# low-voltage-shutoff.net
KiCad netlist of a schematic drawn in EAGLE
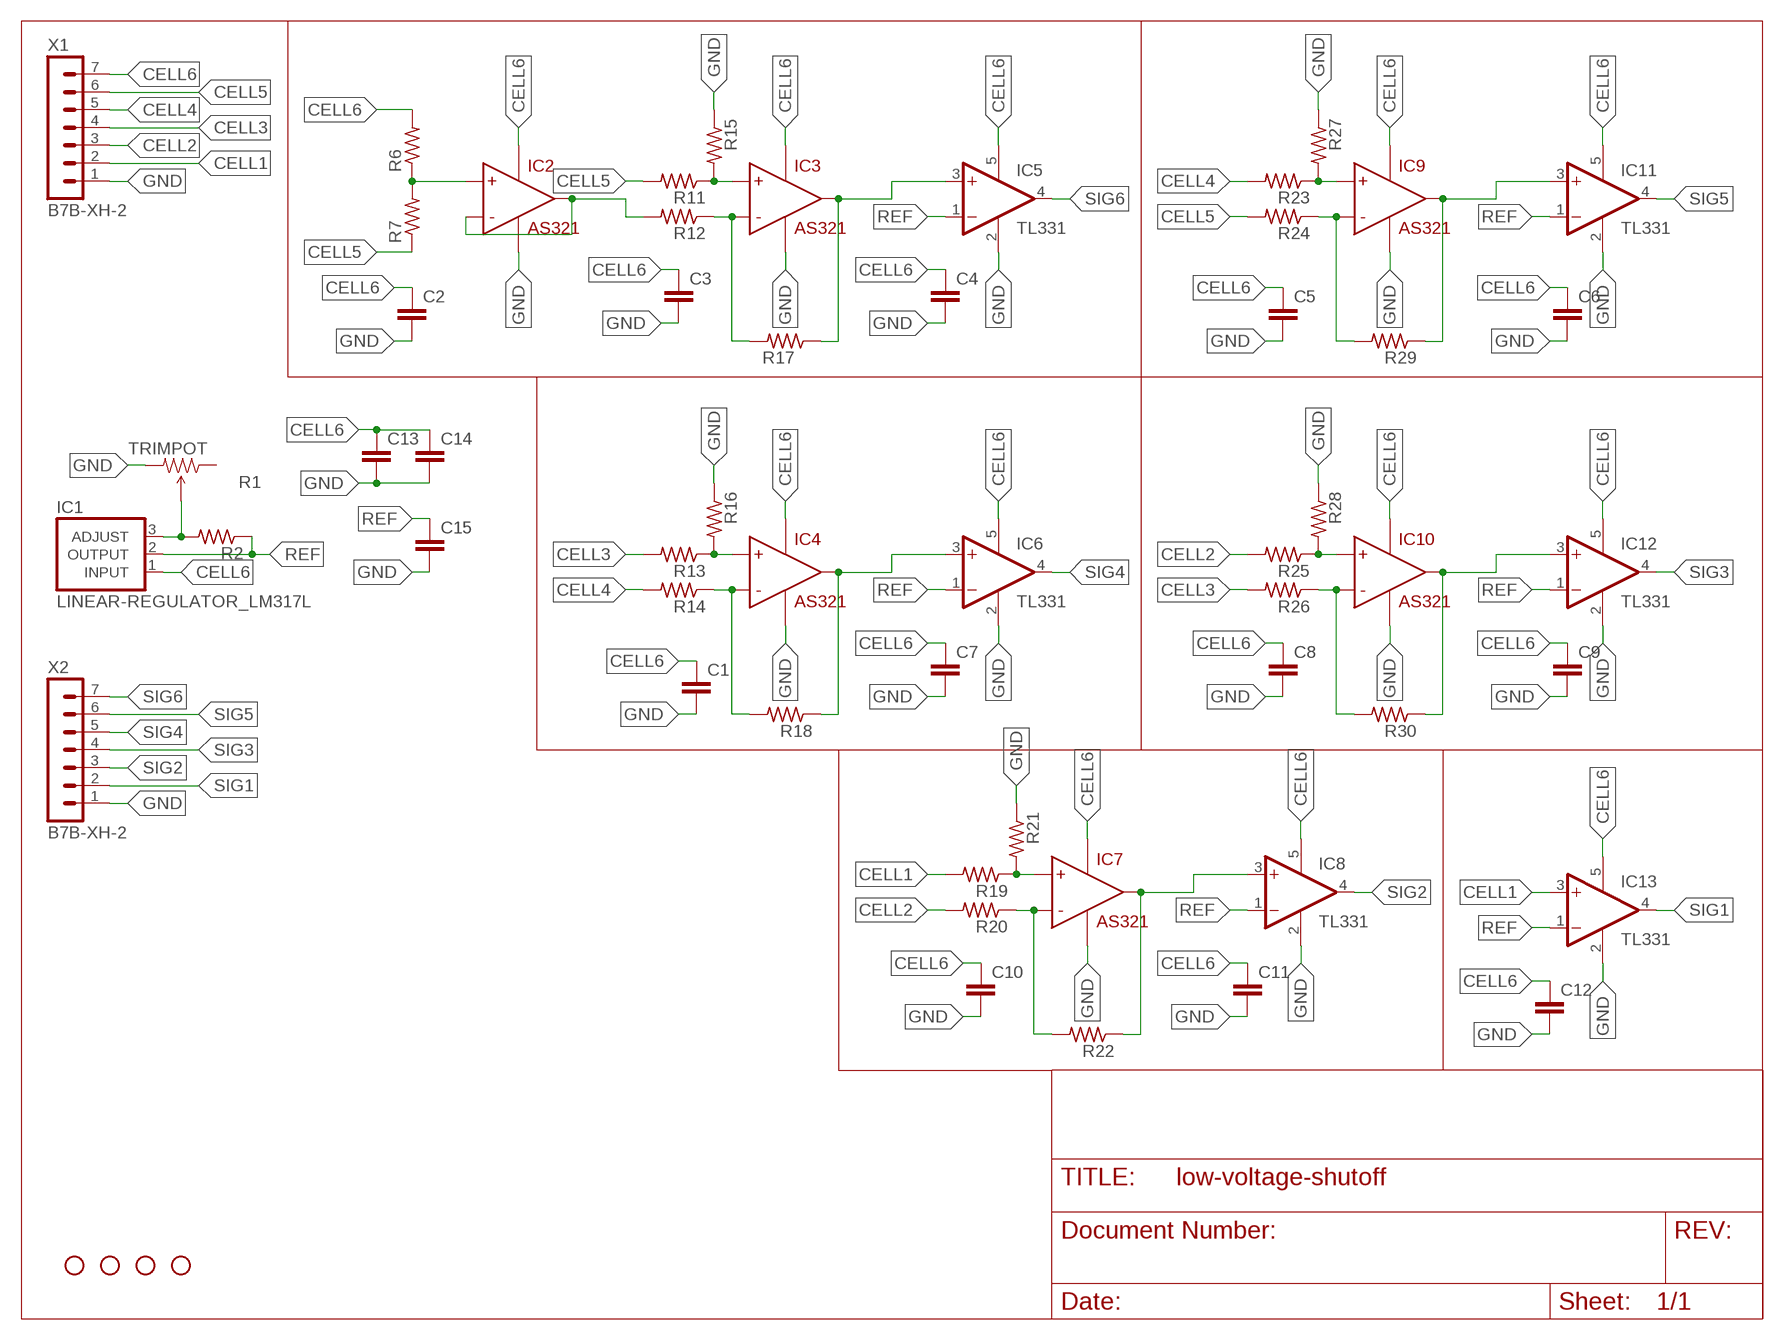
[diagram p0: schematic, sheet 1]

(export (version "E")
  (design (tool "Eeschema 10.0.6"))
  (components
    (comp (ref "C1")
      (value "CAPACITOR_0805")
      (footprint "eagle-import:0805")
      (libsource (lib "eagle-import") (part "CAPACITOR_0805"))
    )
    (comp (ref "C2")
      (value "CAPACITOR_0805")
      (footprint "eagle-import:0805")
      (libsource (lib "eagle-import") (part "CAPACITOR_0805"))
    )
    (comp (ref "C3")
      (value "CAPACITOR_0805")
      (footprint "eagle-import:0805")
      (libsource (lib "eagle-import") (part "CAPACITOR_0805"))
    )
    (comp (ref "C4")
      (value "CAPACITOR_0805")
      (footprint "eagle-import:0805")
      (libsource (lib "eagle-import") (part "CAPACITOR_0805"))
    )
    (comp (ref "C5")
      (value "CAPACITOR_0805")
      (footprint "eagle-import:0805")
      (libsource (lib "eagle-import") (part "CAPACITOR_0805"))
    )
    (comp (ref "C6")
      (value "CAPACITOR_0805")
      (footprint "eagle-import:0805")
      (libsource (lib "eagle-import") (part "CAPACITOR_0805"))
    )
    (comp (ref "C7")
      (value "CAPACITOR_0805")
      (footprint "eagle-import:0805")
      (libsource (lib "eagle-import") (part "CAPACITOR_0805"))
    )
    (comp (ref "C8")
      (value "CAPACITOR_0805")
      (footprint "eagle-import:0805")
      (libsource (lib "eagle-import") (part "CAPACITOR_0805"))
    )
    (comp (ref "C9")
      (value "CAPACITOR_0805")
      (footprint "eagle-import:0805")
      (libsource (lib "eagle-import") (part "CAPACITOR_0805"))
    )
    (comp (ref "C10")
      (value "CAPACITOR_0805")
      (footprint "eagle-import:0805")
      (libsource (lib "eagle-import") (part "CAPACITOR_0805"))
    )
    (comp (ref "C11")
      (value "CAPACITOR_0805")
      (footprint "eagle-import:0805")
      (libsource (lib "eagle-import") (part "CAPACITOR_0805"))
    )
    (comp (ref "C12")
      (value "CAPACITOR_0805")
      (footprint "eagle-import:0805")
      (libsource (lib "eagle-import") (part "CAPACITOR_0805"))
    )
    (comp (ref "C13")
      (value "CAPACITOR_0805")
      (footprint "eagle-import:0805")
      (libsource (lib "eagle-import") (part "CAPACITOR_0805"))
    )
    (comp (ref "C14")
      (value "CAPACITOR_0805")
      (footprint "eagle-import:0805")
      (libsource (lib "eagle-import") (part "CAPACITOR_0805"))
    )
    (comp (ref "C15")
      (value "CAPACITOR_0805")
      (footprint "eagle-import:0805")
      (libsource (lib "eagle-import") (part "CAPACITOR_0805"))
    )
    (comp (ref "H1")
      (value "STAND-OFF")
      (footprint "eagle-import:STAND-OFF")
      (libsource (lib "eagle-import") (part "STAND-OFF"))
    )
    (comp (ref "H2")
      (value "STAND-OFF")
      (footprint "eagle-import:STAND-OFF")
      (libsource (lib "eagle-import") (part "STAND-OFF"))
    )
    (comp (ref "H3")
      (value "STAND-OFF")
      (footprint "eagle-import:STAND-OFF")
      (libsource (lib "eagle-import") (part "STAND-OFF"))
    )
    (comp (ref "H4")
      (value "STAND-OFF")
      (footprint "eagle-import:STAND-OFF")
      (libsource (lib "eagle-import") (part "STAND-OFF"))
    )
    (comp (ref "IC1")
      (value "LINEAR-REGULATOR_LM317L")
      (footprint "eagle-import:TO92")
      (libsource (lib "eagle-import") (part "LINEAR-REGULATOR_LM317L"))
    )
    (comp (ref "IC2")
      (value "AS321")
      (footprint "eagle-import:AS321")
      (libsource (lib "eagle-import") (part "AS321"))
    )
    (comp (ref "IC3")
      (value "AS321")
      (footprint "eagle-import:AS321")
      (libsource (lib "eagle-import") (part "AS321"))
    )
    (comp (ref "IC4")
      (value "AS321")
      (footprint "eagle-import:AS321")
      (libsource (lib "eagle-import") (part "AS321"))
    )
    (comp (ref "IC5")
      (value "TL331")
      (footprint "eagle-import:DBV-R-PDSO-G5")
      (libsource (lib "eagle-import") (part "TL331"))
    )
    (comp (ref "IC6")
      (value "TL331")
      (footprint "eagle-import:DBV-R-PDSO-G5")
      (libsource (lib "eagle-import") (part "TL331"))
    )
    (comp (ref "IC7")
      (value "AS321")
      (footprint "eagle-import:AS321")
      (libsource (lib "eagle-import") (part "AS321"))
    )
    (comp (ref "IC8")
      (value "TL331")
      (footprint "eagle-import:DBV-R-PDSO-G5")
      (libsource (lib "eagle-import") (part "TL331"))
    )
    (comp (ref "IC9")
      (value "AS321")
      (footprint "eagle-import:AS321")
      (libsource (lib "eagle-import") (part "AS321"))
    )
    (comp (ref "IC10")
      (value "AS321")
      (footprint "eagle-import:AS321")
      (libsource (lib "eagle-import") (part "AS321"))
    )
    (comp (ref "IC11")
      (value "TL331")
      (footprint "eagle-import:DBV-R-PDSO-G5")
      (libsource (lib "eagle-import") (part "TL331"))
    )
    (comp (ref "IC12")
      (value "TL331")
      (footprint "eagle-import:DBV-R-PDSO-G5")
      (libsource (lib "eagle-import") (part "TL331"))
    )
    (comp (ref "IC13")
      (value "TL331")
      (footprint "eagle-import:DBV-R-PDSO-G5")
      (libsource (lib "eagle-import") (part "TL331"))
    )
    (comp (ref "R1")
      (value "TRIMPOT")
      (footprint "eagle-import:490-2877-ND")
      (libsource (lib "eagle-import") (part "TRIMPOT"))
    )
    (comp (ref "R2")
      (value "R-US_R0805")
      (footprint "eagle-import:R0805")
      (libsource (lib "eagle-import") (part "R-US_R0805"))
    )
    (comp (ref "R6")
      (value "R-US_R0805")
      (footprint "eagle-import:R0805")
      (libsource (lib "eagle-import") (part "R-US_R0805"))
    )
    (comp (ref "R7")
      (value "R-US_R0805")
      (footprint "eagle-import:R0805")
      (libsource (lib "eagle-import") (part "R-US_R0805"))
    )
    (comp (ref "R11")
      (value "R-US_R0805")
      (footprint "eagle-import:R0805")
      (libsource (lib "eagle-import") (part "R-US_R0805"))
    )
    (comp (ref "R12")
      (value "R-US_R0805")
      (footprint "eagle-import:R0805")
      (libsource (lib "eagle-import") (part "R-US_R0805"))
    )
    (comp (ref "R13")
      (value "R-US_R0805")
      (footprint "eagle-import:R0805")
      (libsource (lib "eagle-import") (part "R-US_R0805"))
    )
    (comp (ref "R14")
      (value "R-US_R0805")
      (footprint "eagle-import:R0805")
      (libsource (lib "eagle-import") (part "R-US_R0805"))
    )
    (comp (ref "R15")
      (value "R-US_R0805")
      (footprint "eagle-import:R0805")
      (libsource (lib "eagle-import") (part "R-US_R0805"))
    )
    (comp (ref "R16")
      (value "R-US_R0805")
      (footprint "eagle-import:R0805")
      (libsource (lib "eagle-import") (part "R-US_R0805"))
    )
    (comp (ref "R17")
      (value "R-US_R0805")
      (footprint "eagle-import:R0805")
      (libsource (lib "eagle-import") (part "R-US_R0805"))
    )
    (comp (ref "R18")
      (value "R-US_R0805")
      (footprint "eagle-import:R0805")
      (libsource (lib "eagle-import") (part "R-US_R0805"))
    )
    (comp (ref "R19")
      (value "R-US_R0805")
      (footprint "eagle-import:R0805")
      (libsource (lib "eagle-import") (part "R-US_R0805"))
    )
    (comp (ref "R20")
      (value "R-US_R0805")
      (footprint "eagle-import:R0805")
      (libsource (lib "eagle-import") (part "R-US_R0805"))
    )
    (comp (ref "R21")
      (value "R-US_R0805")
      (footprint "eagle-import:R0805")
      (libsource (lib "eagle-import") (part "R-US_R0805"))
    )
    (comp (ref "R22")
      (value "R-US_R0805")
      (footprint "eagle-import:R0805")
      (libsource (lib "eagle-import") (part "R-US_R0805"))
    )
    (comp (ref "R23")
      (value "R-US_R0805")
      (footprint "eagle-import:R0805")
      (libsource (lib "eagle-import") (part "R-US_R0805"))
    )
    (comp (ref "R24")
      (value "R-US_R0805")
      (footprint "eagle-import:R0805")
      (libsource (lib "eagle-import") (part "R-US_R0805"))
    )
    (comp (ref "R25")
      (value "R-US_R0805")
      (footprint "eagle-import:R0805")
      (libsource (lib "eagle-import") (part "R-US_R0805"))
    )
    (comp (ref "R26")
      (value "R-US_R0805")
      (footprint "eagle-import:R0805")
      (libsource (lib "eagle-import") (part "R-US_R0805"))
    )
    (comp (ref "R27")
      (value "R-US_R0805")
      (footprint "eagle-import:R0805")
      (libsource (lib "eagle-import") (part "R-US_R0805"))
    )
    (comp (ref "R28")
      (value "R-US_R0805")
      (footprint "eagle-import:R0805")
      (libsource (lib "eagle-import") (part "R-US_R0805"))
    )
    (comp (ref "R29")
      (value "R-US_R0805")
      (footprint "eagle-import:R0805")
      (libsource (lib "eagle-import") (part "R-US_R0805"))
    )
    (comp (ref "R30")
      (value "R-US_R0805")
      (footprint "eagle-import:R0805")
      (libsource (lib "eagle-import") (part "R-US_R0805"))
    )
    (comp (ref "X1")
      (value "B7B-XH-2")
      (footprint "eagle-import:B7B-XH-A")
      (libsource (lib "eagle-import") (part "B7B-XH-2"))
    )
    (comp (ref "X2")
      (value "B7B-XH-2")
      (footprint "eagle-import:B7B-XH-A")
      (libsource (lib "eagle-import") (part "B7B-XH-2"))
    )
  )
  (nets
    (net (code "1") (name "CELL1") (class "Default")
      (node (ref "IC13") (pin "3") (pinfunction "+IN_3") (pintype "input"))
      (node (ref "R19") (pin "2") (pinfunction "2_2") (pintype "passive"))
      (node (ref "X1") (pin "2") (pinfunction "2_2") (pintype "passive"))
    )
    (net (code "2") (name "CELL2") (class "Default")
      (node (ref "R20") (pin "2") (pinfunction "2_2") (pintype "passive"))
      (node (ref "R25") (pin "2") (pinfunction "2_2") (pintype "passive"))
      (node (ref "X1") (pin "3") (pinfunction "3_3") (pintype "passive"))
    )
    (net (code "3") (name "CELL3") (class "Default")
      (node (ref "R13") (pin "2") (pinfunction "2_2") (pintype "passive"))
      (node (ref "R26") (pin "2") (pinfunction "2_2") (pintype "passive"))
      (node (ref "X1") (pin "4") (pinfunction "4_4") (pintype "passive"))
    )
    (net (code "4") (name "CELL4") (class "Default")
      (node (ref "R14") (pin "2") (pinfunction "2_2") (pintype "passive"))
      (node (ref "R23") (pin "2") (pinfunction "2_2") (pintype "passive"))
      (node (ref "X1") (pin "5") (pinfunction "5_5") (pintype "passive"))
    )
    (net (code "5") (name "CELL5") (class "Default")
      (node (ref "R11") (pin "2") (pinfunction "2_2") (pintype "passive"))
      (node (ref "R24") (pin "2") (pinfunction "2_2") (pintype "passive"))
      (node (ref "R7") (pin "1") (pinfunction "1_1") (pintype "passive"))
      (node (ref "X1") (pin "6") (pinfunction "6_6") (pintype "passive"))
    )
    (net (code "6") (name "CELL6") (class "Default")
      (node (ref "C1") (pin "1") (pinfunction "1_1") (pintype "passive"))
      (node (ref "C10") (pin "1") (pinfunction "1_1") (pintype "passive"))
      (node (ref "C11") (pin "1") (pinfunction "1_1") (pintype "passive"))
      (node (ref "C12") (pin "1") (pinfunction "1_1") (pintype "passive"))
      (node (ref "C13") (pin "1") (pinfunction "1_1") (pintype "passive"))
      (node (ref "C14") (pin "1") (pinfunction "1_1") (pintype "passive"))
      (node (ref "C2") (pin "1") (pinfunction "1_1") (pintype "passive"))
      (node (ref "C3") (pin "1") (pinfunction "1_1") (pintype "passive"))
      (node (ref "C4") (pin "1") (pinfunction "1_1") (pintype "passive"))
      (node (ref "C5") (pin "1") (pinfunction "1_1") (pintype "passive"))
      (node (ref "C6") (pin "1") (pinfunction "1_1") (pintype "passive"))
      (node (ref "C7") (pin "1") (pinfunction "1_1") (pintype "passive"))
      (node (ref "C8") (pin "1") (pinfunction "1_1") (pintype "passive"))
      (node (ref "C9") (pin "1") (pinfunction "1_1") (pintype "passive"))
      (node (ref "IC1") (pin "1") (pinfunction "INPUT_1") (pintype "bidirectional"))
      (node (ref "IC10") (pin "5") (pinfunction "V+_5") (pintype "bidirectional"))
      (node (ref "IC11") (pin "5") (pinfunction "V+_5") (pintype "power_in"))
      (node (ref "IC12") (pin "5") (pinfunction "V+_5") (pintype "power_in"))
      (node (ref "IC13") (pin "5") (pinfunction "V+_5") (pintype "power_in"))
      (node (ref "IC2") (pin "5") (pinfunction "V+_5") (pintype "bidirectional"))
      (node (ref "IC3") (pin "5") (pinfunction "V+_5") (pintype "bidirectional"))
      (node (ref "IC4") (pin "5") (pinfunction "V+_5") (pintype "bidirectional"))
      (node (ref "IC5") (pin "5") (pinfunction "V+_5") (pintype "power_in"))
      (node (ref "IC6") (pin "5") (pinfunction "V+_5") (pintype "power_in"))
      (node (ref "IC7") (pin "5") (pinfunction "V+_5") (pintype "bidirectional"))
      (node (ref "IC8") (pin "5") (pinfunction "V+_5") (pintype "power_in"))
      (node (ref "IC9") (pin "5") (pinfunction "V+_5") (pintype "bidirectional"))
      (node (ref "R6") (pin "2") (pinfunction "2_2") (pintype "passive"))
      (node (ref "X1") (pin "7") (pinfunction "7_7") (pintype "passive"))
    )
    (net (code "7") (name "GND") (class "Default")
      (node (ref "C1") (pin "2") (pinfunction "2_2") (pintype "passive"))
      (node (ref "C10") (pin "2") (pinfunction "2_2") (pintype "passive"))
      (node (ref "C11") (pin "2") (pinfunction "2_2") (pintype "passive"))
      (node (ref "C12") (pin "2") (pinfunction "2_2") (pintype "passive"))
      (node (ref "C13") (pin "2") (pinfunction "2_2") (pintype "passive"))
      (node (ref "C14") (pin "2") (pinfunction "2_2") (pintype "passive"))
      (node (ref "C15") (pin "2") (pinfunction "2_2") (pintype "passive"))
      (node (ref "C2") (pin "2") (pinfunction "2_2") (pintype "passive"))
      (node (ref "C3") (pin "2") (pinfunction "2_2") (pintype "passive"))
      (node (ref "C4") (pin "2") (pinfunction "2_2") (pintype "passive"))
      (node (ref "C5") (pin "2") (pinfunction "2_2") (pintype "passive"))
      (node (ref "C6") (pin "2") (pinfunction "2_2") (pintype "passive"))
      (node (ref "C7") (pin "2") (pinfunction "2_2") (pintype "passive"))
      (node (ref "C8") (pin "2") (pinfunction "2_2") (pintype "passive"))
      (node (ref "C9") (pin "2") (pinfunction "2_2") (pintype "passive"))
      (node (ref "IC10") (pin "2") (pinfunction "V-_2") (pintype "bidirectional"))
      (node (ref "IC11") (pin "2") (pinfunction "GND_2") (pintype "power_in"))
      (node (ref "IC12") (pin "2") (pinfunction "GND_2") (pintype "power_in"))
      (node (ref "IC13") (pin "2") (pinfunction "GND_2") (pintype "power_in"))
      (node (ref "IC2") (pin "2") (pinfunction "V-_2") (pintype "bidirectional"))
      (node (ref "IC3") (pin "2") (pinfunction "V-_2") (pintype "bidirectional"))
      (node (ref "IC4") (pin "2") (pinfunction "V-_2") (pintype "bidirectional"))
      (node (ref "IC5") (pin "2") (pinfunction "GND_2") (pintype "power_in"))
      (node (ref "IC6") (pin "2") (pinfunction "GND_2") (pintype "power_in"))
      (node (ref "IC7") (pin "2") (pinfunction "V-_2") (pintype "bidirectional"))
      (node (ref "IC8") (pin "2") (pinfunction "GND_2") (pintype "power_in"))
      (node (ref "IC9") (pin "2") (pinfunction "V-_2") (pintype "bidirectional"))
      (node (ref "R1") (pin "P$3") (pinfunction "CW_P$3") (pintype "passive"))
      (node (ref "R15") (pin "1") (pinfunction "1_1") (pintype "passive"))
      (node (ref "R16") (pin "1") (pinfunction "1_1") (pintype "passive"))
      (node (ref "R21") (pin "1") (pinfunction "1_1") (pintype "passive"))
      (node (ref "R27") (pin "1") (pinfunction "1_1") (pintype "passive"))
      (node (ref "R28") (pin "1") (pinfunction "1_1") (pintype "passive"))
      (node (ref "X1") (pin "1") (pinfunction "1_1") (pintype "passive"))
      (node (ref "X2") (pin "1") (pinfunction "1_1") (pintype "passive"))
    )
    (net (code "8") (name "Net-(IC1-ADJUST)") (class "Default")
      (node (ref "IC1") (pin "3") (pinfunction "ADJUST_3") (pintype "bidirectional"))
      (node (ref "R1") (pin "P$2") (pinfunction "WIPER_P$2") (pintype "passive"))
      (node (ref "R2") (pin "2") (pinfunction "2_2") (pintype "passive"))
    )
    (net (code "9") (name "Net-(IC2-I+)") (class "Default")
      (node (ref "IC2") (pin "1") (pinfunction "I+_1") (pintype "bidirectional"))
      (node (ref "R6") (pin "1") (pinfunction "1_1") (pintype "passive"))
      (node (ref "R7") (pin "2") (pinfunction "2_2") (pintype "passive"))
    )
    (net (code "10") (name "Net-(IC2-I-)") (class "Default")
      (node (ref "IC2") (pin "3") (pinfunction "I-_3") (pintype "bidirectional"))
      (node (ref "IC2") (pin "4") (pinfunction "OUT_4") (pintype "bidirectional"))
      (node (ref "R12") (pin "2") (pinfunction "2_2") (pintype "passive"))
    )
    (net (code "11") (name "Net-(IC3-I+)") (class "Default")
      (node (ref "IC3") (pin "1") (pinfunction "I+_1") (pintype "bidirectional"))
      (node (ref "R11") (pin "1") (pinfunction "1_1") (pintype "passive"))
      (node (ref "R15") (pin "2") (pinfunction "2_2") (pintype "passive"))
    )
    (net (code "12") (name "Net-(IC3-I-)") (class "Default")
      (node (ref "IC3") (pin "3") (pinfunction "I-_3") (pintype "bidirectional"))
      (node (ref "R12") (pin "1") (pinfunction "1_1") (pintype "passive"))
      (node (ref "R17") (pin "2") (pinfunction "2_2") (pintype "passive"))
    )
    (net (code "13") (name "Net-(IC3-OUT)") (class "Default")
      (node (ref "IC3") (pin "4") (pinfunction "OUT_4") (pintype "bidirectional"))
      (node (ref "IC5") (pin "3") (pinfunction "+IN_3") (pintype "input"))
      (node (ref "R17") (pin "1") (pinfunction "1_1") (pintype "passive"))
    )
    (net (code "14") (name "Net-(IC4-I+)") (class "Default")
      (node (ref "IC4") (pin "1") (pinfunction "I+_1") (pintype "bidirectional"))
      (node (ref "R13") (pin "1") (pinfunction "1_1") (pintype "passive"))
      (node (ref "R16") (pin "2") (pinfunction "2_2") (pintype "passive"))
    )
    (net (code "15") (name "Net-(IC4-I-)") (class "Default")
      (node (ref "IC4") (pin "3") (pinfunction "I-_3") (pintype "bidirectional"))
      (node (ref "R14") (pin "1") (pinfunction "1_1") (pintype "passive"))
      (node (ref "R18") (pin "2") (pinfunction "2_2") (pintype "passive"))
    )
    (net (code "16") (name "Net-(IC4-OUT)") (class "Default")
      (node (ref "IC4") (pin "4") (pinfunction "OUT_4") (pintype "bidirectional"))
      (node (ref "IC6") (pin "3") (pinfunction "+IN_3") (pintype "input"))
      (node (ref "R18") (pin "1") (pinfunction "1_1") (pintype "passive"))
    )
    (net (code "17") (name "Net-(IC7-I+)") (class "Default")
      (node (ref "IC7") (pin "1") (pinfunction "I+_1") (pintype "bidirectional"))
      (node (ref "R19") (pin "1") (pinfunction "1_1") (pintype "passive"))
      (node (ref "R21") (pin "2") (pinfunction "2_2") (pintype "passive"))
    )
    (net (code "18") (name "Net-(IC7-I-)") (class "Default")
      (node (ref "IC7") (pin "3") (pinfunction "I-_3") (pintype "bidirectional"))
      (node (ref "R20") (pin "1") (pinfunction "1_1") (pintype "passive"))
      (node (ref "R22") (pin "2") (pinfunction "2_2") (pintype "passive"))
    )
    (net (code "19") (name "Net-(IC7-OUT)") (class "Default")
      (node (ref "IC7") (pin "4") (pinfunction "OUT_4") (pintype "bidirectional"))
      (node (ref "IC8") (pin "3") (pinfunction "+IN_3") (pintype "input"))
      (node (ref "R22") (pin "1") (pinfunction "1_1") (pintype "passive"))
    )
    (net (code "20") (name "Net-(IC9-I+)") (class "Default")
      (node (ref "IC9") (pin "1") (pinfunction "I+_1") (pintype "bidirectional"))
      (node (ref "R23") (pin "1") (pinfunction "1_1") (pintype "passive"))
      (node (ref "R27") (pin "2") (pinfunction "2_2") (pintype "passive"))
    )
    (net (code "21") (name "Net-(IC9-I-)") (class "Default")
      (node (ref "IC9") (pin "3") (pinfunction "I-_3") (pintype "bidirectional"))
      (node (ref "R24") (pin "1") (pinfunction "1_1") (pintype "passive"))
      (node (ref "R29") (pin "2") (pinfunction "2_2") (pintype "passive"))
    )
    (net (code "22") (name "Net-(IC10-I+)") (class "Default")
      (node (ref "IC10") (pin "1") (pinfunction "I+_1") (pintype "bidirectional"))
      (node (ref "R25") (pin "1") (pinfunction "1_1") (pintype "passive"))
      (node (ref "R28") (pin "2") (pinfunction "2_2") (pintype "passive"))
    )
    (net (code "23") (name "Net-(IC10-I-)") (class "Default")
      (node (ref "IC10") (pin "3") (pinfunction "I-_3") (pintype "bidirectional"))
      (node (ref "R26") (pin "1") (pinfunction "1_1") (pintype "passive"))
      (node (ref "R30") (pin "2") (pinfunction "2_2") (pintype "passive"))
    )
    (net (code "24") (name "Net-(IC10-OUT)") (class "Default")
      (node (ref "IC10") (pin "4") (pinfunction "OUT_4") (pintype "bidirectional"))
      (node (ref "IC12") (pin "3") (pinfunction "+IN_3") (pintype "input"))
      (node (ref "R30") (pin "1") (pinfunction "1_1") (pintype "passive"))
    )
    (net (code "25") (name "Net-(IC11-+IN)") (class "Default")
      (node (ref "IC11") (pin "3") (pinfunction "+IN_3") (pintype "input"))
      (node (ref "IC9") (pin "4") (pinfunction "OUT_4") (pintype "bidirectional"))
      (node (ref "R29") (pin "1") (pinfunction "1_1") (pintype "passive"))
    )
    (net (code "26") (name "REF") (class "Default")
      (node (ref "C15") (pin "1") (pinfunction "1_1") (pintype "passive"))
      (node (ref "IC1") (pin "2") (pinfunction "OUTPUT_2") (pintype "bidirectional"))
      (node (ref "IC11") (pin "1") (pinfunction "-IN_1") (pintype "input"))
      (node (ref "IC12") (pin "1") (pinfunction "-IN_1") (pintype "input"))
      (node (ref "IC13") (pin "1") (pinfunction "-IN_1") (pintype "input"))
      (node (ref "IC5") (pin "1") (pinfunction "-IN_1") (pintype "input"))
      (node (ref "IC6") (pin "1") (pinfunction "-IN_1") (pintype "input"))
      (node (ref "IC8") (pin "1") (pinfunction "-IN_1") (pintype "input"))
      (node (ref "R2") (pin "1") (pinfunction "1_1") (pintype "passive"))
    )
    (net (code "27") (name "SIG1") (class "Default")
      (node (ref "IC13") (pin "4") (pinfunction "OUT_4") (pintype "output"))
      (node (ref "X2") (pin "2") (pinfunction "2_2") (pintype "passive"))
    )
    (net (code "28") (name "SIG2") (class "Default")
      (node (ref "IC8") (pin "4") (pinfunction "OUT_4") (pintype "output"))
      (node (ref "X2") (pin "3") (pinfunction "3_3") (pintype "passive"))
    )
    (net (code "29") (name "SIG3") (class "Default")
      (node (ref "IC12") (pin "4") (pinfunction "OUT_4") (pintype "output"))
      (node (ref "X2") (pin "4") (pinfunction "4_4") (pintype "passive"))
    )
    (net (code "30") (name "SIG4") (class "Default")
      (node (ref "IC6") (pin "4") (pinfunction "OUT_4") (pintype "output"))
      (node (ref "X2") (pin "5") (pinfunction "5_5") (pintype "passive"))
    )
    (net (code "31") (name "SIG5") (class "Default")
      (node (ref "IC11") (pin "4") (pinfunction "OUT_4") (pintype "output"))
      (node (ref "X2") (pin "6") (pinfunction "6_6") (pintype "passive"))
    )
    (net (code "32") (name "SIG6") (class "Default")
      (node (ref "IC5") (pin "4") (pinfunction "OUT_4") (pintype "output"))
      (node (ref "X2") (pin "7") (pinfunction "7_7") (pintype "passive"))
    )
    (net (code "33") (name "unconnected-(R1-CCW-PadP$1)") (class "Default")
      (node (ref "R1") (pin "P$1") (pinfunction "CCW_P$1") (pintype "passive"))
    )
  )
)
